# Raspberry_Pwr.net
KiCad netlist of a schematic drawn in Altium Designer
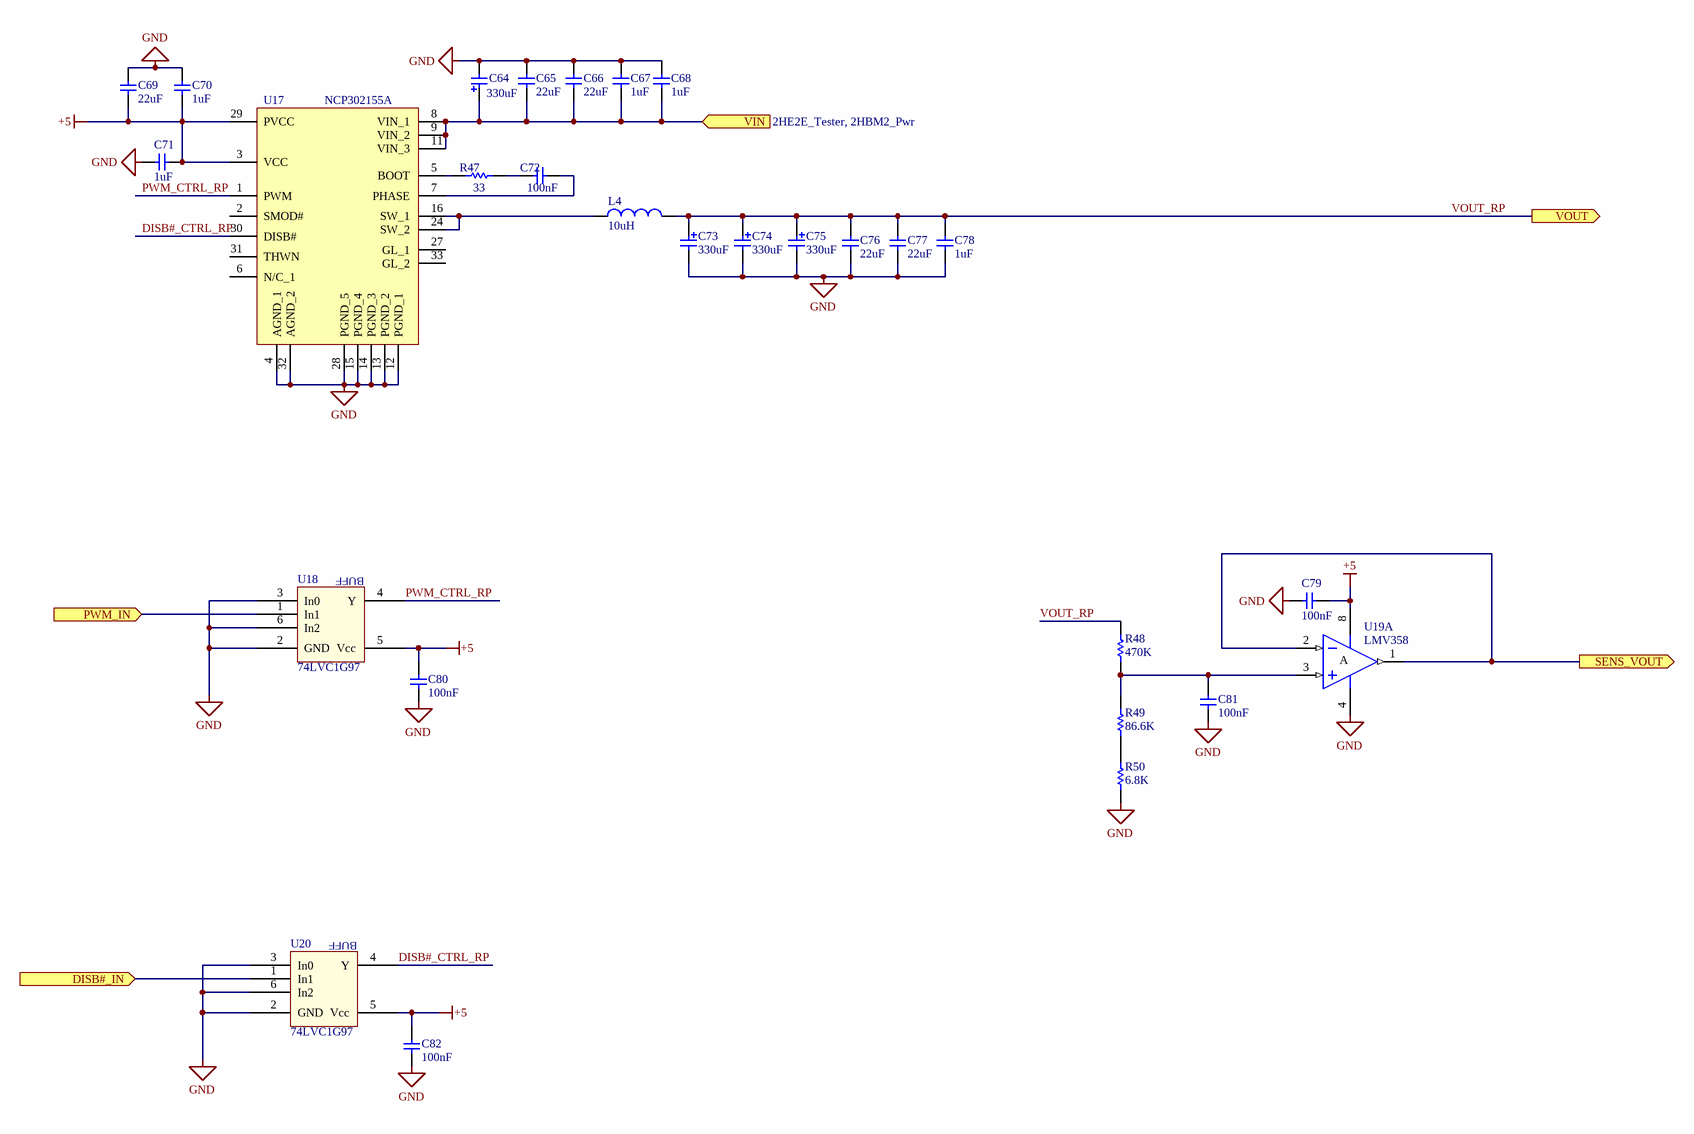
[diagram p0: Raspberry_Pwr.SchDoc]

(export (version "E")
  (design (tool "Eeschema 10.0.6"))
  (components
    (comp (ref "C64")
      (value "330uF")
      (footprint "Cap Elet SMD 8.0 mm CASE E-h6.5mm")
      (description "Condensatore elettrolitico 35V D8")
      (fields (field (name "Comment") "Cap Elettrolitico"))
      (libsource (lib "Plume") (part "Cap Elettrolitico"))
    )
    (comp (ref "C65")
      (value "22uF")
      (footprint "1206M")
      (description "Ceramic Capacitor 25V")
      (fields (field (name "Comment") "Cap Ceramic"))
      (libsource (lib "Plume") (part "Cap Ceramic"))
    )
    (comp (ref "C66")
      (value "22uF")
      (footprint "1206M")
      (description "Ceramic Capacitor 25V")
      (fields (field (name "Comment") "Cap Ceramic"))
      (libsource (lib "Plume") (part "Cap Ceramic"))
    )
    (comp (ref "C67")
      (value "1uF")
      (footprint "1206M")
      (description "Ceramic Capacitor 50V")
      (fields (field (name "Comment") "Cap Ceramic"))
      (libsource (lib "Plume") (part "Cap Ceramic"))
    )
    (comp (ref "C68")
      (value "1uF")
      (footprint "1206M")
      (description "Ceramic Capacitor 50V")
      (fields (field (name "Comment") "Cap Ceramic"))
      (libsource (lib "Plume") (part "Cap Ceramic"))
    )
    (comp (ref "C69")
      (value "22uF")
      (footprint "1206M")
      (description "Ceramic Capacitor 25V")
      (fields (field (name "Comment") "Cap Ceramic"))
      (libsource (lib "Plume") (part "Cap Ceramic"))
    )
    (comp (ref "C70")
      (value "1uF")
      (footprint "1206M")
      (description "Ceramic Capacitor 50V")
      (fields (field (name "Comment") "Cap Ceramic"))
      (libsource (lib "Plume") (part "Cap Ceramic"))
    )
    (comp (ref "C71")
      (value "1uF")
      (footprint "1206M")
      (description "Ceramic Capacitor 50V")
      (fields (field (name "Comment") "Cap Ceramic"))
      (libsource (lib "Plume") (part "Cap Ceramic"))
    )
    (comp (ref "C72")
      (value "100nF")
      (footprint "0603M-C")
      (description "Ceramic Capacitor")
      (fields (field (name "Comment") "Cap Ceramic"))
      (libsource (lib "Plume") (part "Cap Ceramic"))
    )
    (comp (ref "C73")
      (value "330uF")
      (footprint "Cap Elet SMD 8.0 mm CASE E-h6.5mm")
      (description "Condensatore elettrolitico 35V D8")
      (fields (field (name "Comment") "Cap Elettrolitico"))
      (libsource (lib "Plume") (part "Cap Elettrolitico"))
    )
    (comp (ref "C74")
      (value "330uF")
      (footprint "Cap Elet SMD 8.0 mm CASE E-h6.5mm")
      (description "Condensatore elettrolitico 35V D8")
      (fields (field (name "Comment") "Cap Elettrolitico"))
      (libsource (lib "Plume") (part "Cap Elettrolitico"))
    )
    (comp (ref "C75")
      (value "330uF")
      (footprint "Cap Elet SMD 8.0 mm CASE E-h6.5mm")
      (description "Condensatore elettrolitico 35V D8")
      (fields (field (name "Comment") "Cap Elettrolitico"))
      (libsource (lib "Plume") (part "Cap Elettrolitico"))
    )
    (comp (ref "C76")
      (value "22uF")
      (footprint "1206M")
      (description "Ceramic Capacitor 25V")
      (fields (field (name "Comment") "Cap Ceramic"))
      (libsource (lib "Plume") (part "Cap Ceramic"))
    )
    (comp (ref "C77")
      (value "22uF")
      (footprint "1206M")
      (description "Ceramic Capacitor 25V")
      (fields (field (name "Comment") "Cap Ceramic"))
      (libsource (lib "Plume") (part "Cap Ceramic"))
    )
    (comp (ref "C78")
      (value "1uF")
      (footprint "1206M")
      (description "Ceramic Capacitor 50V")
      (fields (field (name "Comment") "Cap Ceramic"))
      (libsource (lib "Plume") (part "Cap Ceramic"))
    )
    (comp (ref "C79")
      (value "100nF")
      (footprint "0603M")
      (description "Ceramic Capacitor 25V")
      (fields (field (name "Comment") "Cap Ceramic"))
      (libsource (lib "Plume") (part "Cap Ceramic"))
    )
    (comp (ref "C80")
      (value "100nF")
      (footprint "0603M")
      (description "Ceramic Capacitor 25V")
      (fields (field (name "Comment") "Cap Ceramic"))
      (libsource (lib "Plume") (part "Cap Ceramic"))
    )
    (comp (ref "C81")
      (value "100nF")
      (footprint "0603M")
      (description "Ceramic Capacitor 25V")
      (fields (field (name "Comment") "Cap Ceramic"))
      (libsource (lib "Plume") (part "Cap Ceramic"))
    )
    (comp (ref "C82")
      (value "100nF")
      (footprint "0603M")
      (description "Ceramic Capacitor 25V")
      (fields (field (name "Comment") "Cap Ceramic"))
      (libsource (lib "Plume") (part "Cap Ceramic"))
    )
    (comp (ref "L4")
      (value "10uH")
      (footprint "WE-HCC_1210")
      (description "WE 7443321000")
      (fields (field (name "Comment") "Induttanza"))
      (libsource (lib "Plume") (part "Induttanza"))
    )
    (comp (ref "R47")
      (value "33")
      (footprint "0603M")
      (description "Resistor")
      (libsource (lib "Plume") (part "Resistor"))
    )
    (comp (ref "R48")
      (value "470K")
      (footprint "0603M")
      (description "Resistor")
      (libsource (lib "Plume") (part "Resistor"))
    )
    (comp (ref "R49")
      (value "86.6K")
      (footprint "0603M")
      (description "Resistor")
      (libsource (lib "Plume") (part "Resistor"))
    )
    (comp (ref "R50")
      (value "6.8K")
      (footprint "0603M")
      (description "Resistor")
      (libsource (lib "Plume") (part "Resistor"))
    )
    (comp (ref "U17")
      (value "NCP302155A")
      (footprint "NCP302155A")
      (description "Integrated Driver and MOSFET")
      (libsource (lib "Plume") (part "NCP302155A"))
    )
    (comp (ref "U18")
      (value "74LVC1G97")
      (footprint "TSOP65P211-6N")
      (description "Logic gate configurabile")
      (libsource (lib "Plume") (part "74LVC1G97"))
    )
    (comp (ref "U19")
      (value "LMV358")
      (footprint "SOIC127P600-8N")
      (description "Dual Operational Amplifier Single Supply Rail to Rail")
      (fields (field (name "PUBLISHER") "Altium Limited"))
      (libsource (lib "Plume") (part "LMV358"))
    )
    (comp (ref "U20")
      (value "74LVC1G97")
      (footprint "TSOP65P211-6N")
      (description "Logic gate configurabile")
      (libsource (lib "Plume") (part "74LVC1G97"))
    )
  )
  (nets
    (net (code "1") (name "+5") (class "Default")
      (node (ref "C69") (pin "2") (pinfunction "2_2") (pintype "passive"))
      (node (ref "C70") (pin "1") (pinfunction "1_1") (pintype "passive"))
      (node (ref "C71") (pin "1") (pinfunction "1_1") (pintype "passive"))
      (node (ref "C79") (pin "2") (pinfunction "2_2") (pintype "passive"))
      (node (ref "C80") (pin "2") (pinfunction "2_2") (pintype "passive"))
      (node (ref "C82") (pin "2") (pinfunction "2_2") (pintype "passive"))
      (node (ref "U17") (pin "29") (pinfunction "PVCC_29") (pintype "passive"))
      (node (ref "U17") (pin "3") (pinfunction "VCC_3") (pintype "passive"))
      (node (ref "U18") (pin "5") (pinfunction "Vcc_5") (pintype "passive"))
      (node (ref "U19") (pin "8") (pinfunction "V+_8") (pintype "power_in"))
      (node (ref "U20") (pin "5") (pinfunction "Vcc_5") (pintype "passive"))
    )
    (net (code "2") (name "/DISB#_CTRL_RP") (class "Default")
      (node (ref "U17") (pin "30") (pinfunction "DISB#_30") (pintype "passive"))
      (node (ref "U20") (pin "4") (pinfunction "Y_4") (pintype "passive"))
    )
    (net (code "3") (name "/DISB#_IN") (class "Default")
      (node (ref "U20") (pin "1") (pinfunction "In1_1") (pintype "passive"))
    )
    (net (code "4") (name "/PWM_CTRL_RP") (class "Default")
      (node (ref "U17") (pin "1") (pinfunction "PWM_1") (pintype "passive"))
      (node (ref "U18") (pin "4") (pinfunction "Y_4") (pintype "passive"))
    )
    (net (code "5") (name "/PWM_IN") (class "Default")
      (node (ref "U18") (pin "1") (pinfunction "In1_1") (pintype "passive"))
    )
    (net (code "6") (name "/SENS_VOUT") (class "Default")
      (node (ref "U19") (pin "1") (pinfunction "OUT_1") (pintype "output"))
      (node (ref "U19") (pin "2") (pinfunction "IN-_2") (pintype "input"))
    )
    (net (code "7") (name "/VIN") (class "Default")
      (node (ref "C64") (pin "1") (pinfunction "1_1") (pintype "passive"))
      (node (ref "C65") (pin "1") (pinfunction "1_1") (pintype "passive"))
      (node (ref "C66") (pin "1") (pinfunction "1_1") (pintype "passive"))
      (node (ref "C67") (pin "1") (pinfunction "1_1") (pintype "passive"))
      (node (ref "C68") (pin "1") (pinfunction "1_1") (pintype "passive"))
      (node (ref "U17") (pin "11") (pinfunction "VIN_3_11") (pintype "passive"))
      (node (ref "U17") (pin "8") (pinfunction "VIN_1_8") (pintype "passive"))
      (node (ref "U17") (pin "9") (pinfunction "VIN_2_9") (pintype "passive"))
    )
    (net (code "8") (name "/VOUT_RP") (class "Default")
      (node (ref "C73") (pin "1") (pinfunction "1_1") (pintype "passive"))
      (node (ref "C74") (pin "1") (pinfunction "1_1") (pintype "passive"))
      (node (ref "C75") (pin "1") (pinfunction "1_1") (pintype "passive"))
      (node (ref "C76") (pin "1") (pinfunction "1_1") (pintype "passive"))
      (node (ref "C77") (pin "1") (pinfunction "1_1") (pintype "passive"))
      (node (ref "C78") (pin "1") (pinfunction "1_1") (pintype "passive"))
      (node (ref "L4") (pin "2") (pinfunction "2_2") (pintype "passive"))
      (node (ref "R48") (pin "2") (pinfunction "2_2") (pintype "passive"))
    )
    (net (code "9") (name "GND") (class "Default")
      (node (ref "C64") (pin "2") (pinfunction "2_2") (pintype "passive"))
      (node (ref "C65") (pin "2") (pinfunction "2_2") (pintype "passive"))
      (node (ref "C66") (pin "2") (pinfunction "2_2") (pintype "passive"))
      (node (ref "C67") (pin "2") (pinfunction "2_2") (pintype "passive"))
      (node (ref "C68") (pin "2") (pinfunction "2_2") (pintype "passive"))
      (node (ref "C69") (pin "1") (pinfunction "1_1") (pintype "passive"))
      (node (ref "C70") (pin "2") (pinfunction "2_2") (pintype "passive"))
      (node (ref "C71") (pin "2") (pinfunction "2_2") (pintype "passive"))
      (node (ref "C73") (pin "2") (pinfunction "2_2") (pintype "passive"))
      (node (ref "C74") (pin "2") (pinfunction "2_2") (pintype "passive"))
      (node (ref "C75") (pin "2") (pinfunction "2_2") (pintype "passive"))
      (node (ref "C76") (pin "2") (pinfunction "2_2") (pintype "passive"))
      (node (ref "C77") (pin "2") (pinfunction "2_2") (pintype "passive"))
      (node (ref "C78") (pin "2") (pinfunction "2_2") (pintype "passive"))
      (node (ref "C79") (pin "1") (pinfunction "1_1") (pintype "passive"))
      (node (ref "C80") (pin "1") (pinfunction "1_1") (pintype "passive"))
      (node (ref "C81") (pin "1") (pinfunction "1_1") (pintype "passive"))
      (node (ref "C82") (pin "1") (pinfunction "1_1") (pintype "passive"))
      (node (ref "R50") (pin "1") (pinfunction "1_1") (pintype "passive"))
      (node (ref "U17") (pin "12") (pinfunction "PGND_1_12") (pintype "passive"))
      (node (ref "U17") (pin "13") (pinfunction "PGND_2_13") (pintype "passive"))
      (node (ref "U17") (pin "14") (pinfunction "PGND_3_14") (pintype "passive"))
      (node (ref "U17") (pin "15") (pinfunction "PGND_4_15") (pintype "passive"))
      (node (ref "U17") (pin "28") (pinfunction "PGND_5_28") (pintype "passive"))
      (node (ref "U17") (pin "32") (pinfunction "AGND_2_32") (pintype "passive"))
      (node (ref "U17") (pin "4") (pinfunction "AGND_1_4") (pintype "passive"))
      (node (ref "U18") (pin "2") (pinfunction "GND_2") (pintype "passive"))
      (node (ref "U18") (pin "3") (pinfunction "In0_3") (pintype "passive"))
      (node (ref "U18") (pin "6") (pinfunction "In2_6") (pintype "passive"))
      (node (ref "U19") (pin "4") (pinfunction "GND_4") (pintype "passive"))
      (node (ref "U20") (pin "2") (pinfunction "GND_2") (pintype "passive"))
      (node (ref "U20") (pin "3") (pinfunction "In0_3") (pintype "passive"))
      (node (ref "U20") (pin "6") (pinfunction "In2_6") (pintype "passive"))
    )
    (net (code "10") (name "Net-(C72-Pad1)") (class "Default")
      (node (ref "C72") (pin "1") (pinfunction "1_1") (pintype "passive"))
      (node (ref "R47") (pin "2") (pinfunction "2_2") (pintype "passive"))
    )
    (net (code "11") (name "Net-(R49-Pad1)") (class "Default")
      (node (ref "R49") (pin "1") (pinfunction "1_1") (pintype "passive"))
      (node (ref "R50") (pin "2") (pinfunction "2_2") (pintype "passive"))
    )
    (net (code "12") (name "Net-(U17-BOOT)") (class "Default")
      (node (ref "R47") (pin "1") (pinfunction "1_1") (pintype "passive"))
      (node (ref "U17") (pin "5") (pinfunction "BOOT_5") (pintype "passive"))
    )
    (net (code "13") (name "Net-(U17-PHASE)") (class "Default")
      (node (ref "C72") (pin "2") (pinfunction "2_2") (pintype "passive"))
      (node (ref "U17") (pin "7") (pinfunction "PHASE_7") (pintype "passive"))
    )
    (net (code "14") (name "Net-(U17-SW_1)") (class "Default")
      (node (ref "L4") (pin "1") (pinfunction "1_1") (pintype "passive"))
      (node (ref "U17") (pin "16") (pinfunction "SW_1_16") (pintype "passive"))
      (node (ref "U17") (pin "24") (pinfunction "SW_2_24") (pintype "passive"))
    )
    (net (code "15") (name "Net-(U19A-IN+)") (class "Default")
      (node (ref "C81") (pin "2") (pinfunction "2_2") (pintype "passive"))
      (node (ref "R48") (pin "1") (pinfunction "1_1") (pintype "passive"))
      (node (ref "R49") (pin "2") (pinfunction "2_2") (pintype "passive"))
      (node (ref "U19") (pin "3") (pinfunction "IN+_3") (pintype "input"))
    )
    (net (code "16") (name "unconnected-(U17-GL_1-Pad27)") (class "Default")
      (node (ref "U17") (pin "27") (pinfunction "GL_1_27") (pintype "passive"))
    )
    (net (code "17") (name "unconnected-(U17-GL_2-Pad33)") (class "Default")
      (node (ref "U17") (pin "33") (pinfunction "GL_2_33") (pintype "passive"))
    )
    (net (code "18") (name "unconnected-(U17-N{slash}C_1-Pad6)") (class "Default")
      (node (ref "U17") (pin "6") (pinfunction "N/C_1_6") (pintype "passive"))
    )
    (net (code "19") (name "unconnected-(U17-SMOD#-Pad2)") (class "Default")
      (node (ref "U17") (pin "2") (pinfunction "SMOD#_2") (pintype "passive"))
    )
    (net (code "20") (name "unconnected-(U17-THWN-Pad31)") (class "Default")
      (node (ref "U17") (pin "31") (pinfunction "THWN_31") (pintype "passive"))
    )
  )
)
